# uMultimeter_USB_Sch.net
KiCad netlist of a schematic drawn in Altium Designer
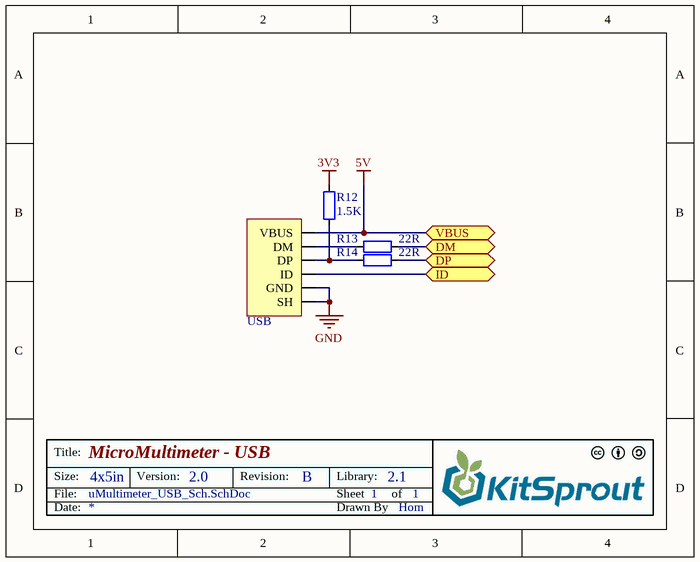
[diagram p0: uMultimeter_USB_Sch.SchDoc]

(export (version "E")
  (design (tool "Eeschema 10.0.6"))
  (components
    (comp (ref "R12")
      (value "1.5K")
      (footprint "PCB_PassiveRes:RES_0603")
      (description "Resistor")
      (fields (field (name "Comment") "Res_0603"))
      (libsource (lib "SCH_Passive") (part "Res_0603"))
    )
    (comp (ref "R13")
      (value "22R")
      (footprint "PCB_PassiveRes:RES_0603")
      (description "Resistor")
      (fields (field (name "Comment") "Res_0603"))
      (libsource (lib "") (part "Res_0603_1"))
    )
    (comp (ref "R14")
      (value "22R")
      (footprint "PCB_PassiveRes:RES_0603")
      (description "Resistor")
      (fields (field (name "Comment") "Res_0603"))
      (libsource (lib "") (part "Res_0603_1"))
    )
    (comp (ref "USB")
      (value "USB_Micro")
      (footprint "PCB_USB:USB_Micro-AB")
      (description "USB")
      (libsource (lib "SCH_USB") (part "USB_Micro"))
    )
  )
  (nets
    (net (code "1") (name "/DM") (class "Default")
      (node (ref "R13") (pin "2") (pinfunction "2_2") (pintype "passive"))
    )
    (net (code "2") (name "/DP") (class "Default")
      (node (ref "R14") (pin "2") (pinfunction "2_2") (pintype "passive"))
    )
    (net (code "3") (name "/ID") (class "Default")
      (node (ref "USB") (pin "4") (pinfunction "ID_4") (pintype "passive"))
    )
    (net (code "4") (name "3V3") (class "Default")
      (node (ref "R12") (pin "1") (pinfunction "1_1") (pintype "passive"))
    )
    (net (code "5") (name "5V") (class "Default")
      (node (ref "USB") (pin "1") (pinfunction "VBUS_1") (pintype "passive"))
    )
    (net (code "6") (name "GND") (class "Default")
      (node (ref "USB") (pin "0") (pinfunction "SH_0") (pintype "passive"))
      (node (ref "USB") (pin "5") (pinfunction "GND_5") (pintype "passive"))
    )
    (net (code "7") (name "Net-(USB-DM)") (class "Default")
      (node (ref "R13") (pin "1") (pinfunction "1_1") (pintype "passive"))
      (node (ref "USB") (pin "2") (pinfunction "DM_2") (pintype "passive"))
    )
    (net (code "8") (name "Net-(USB-DP)") (class "Default")
      (node (ref "R12") (pin "2") (pinfunction "2_2") (pintype "passive"))
      (node (ref "R14") (pin "1") (pinfunction "1_1") (pintype "passive"))
      (node (ref "USB") (pin "3") (pinfunction "DP_3") (pintype "passive"))
    )
  )
)
